# H743X___V1_0__PCB__AD.net
KiCad netlist of a schematic drawn in Altium Designer
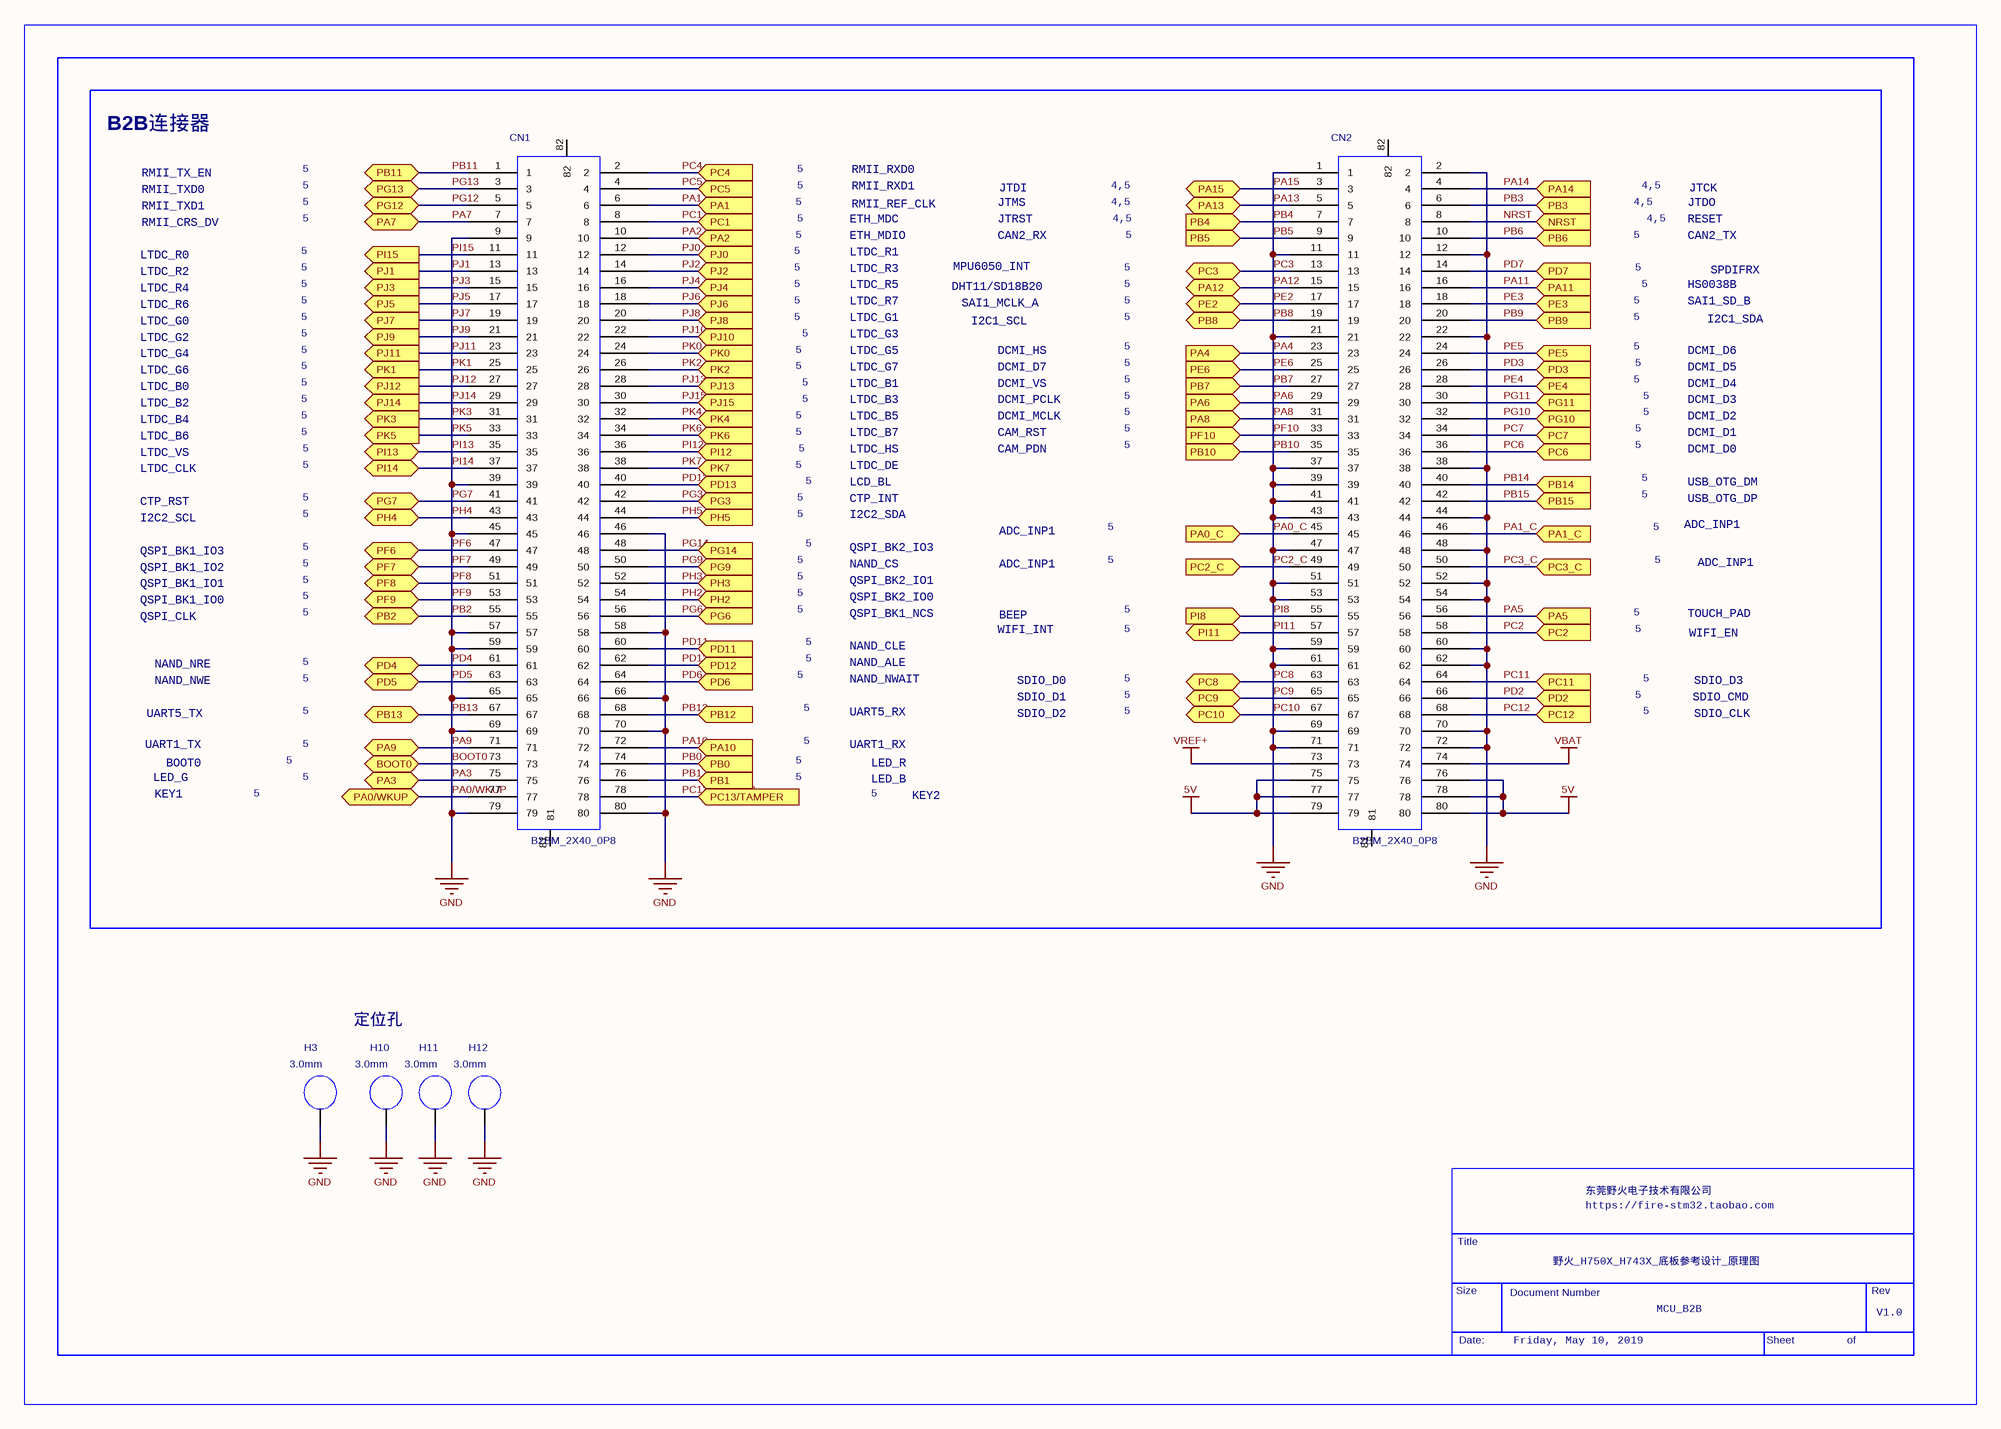
[diagram p0: 野火_H743X_核心板_V1.0_底板原理图和PCB参考设计_AD格式.SchDoc]

(export (version "E")
  (design (tool "Eeschema 10.0.6"))
  (components
    (comp (ref "CN1")
      (value "B2BM_2X40_0P8")
      (footprint "B2BM-2X40-0P8")
      (fields
        (field (name "Comment") "B2BF_2X40_0")
        (field (name "SOURCE_PATH") "F:\\STM32\\H750\\SCH\\野火_H750 PRO底板_原理图_V1_0.DSN")
      )
      (libsource (lib "*") (part "B2BF_2X40_0"))
    )
    (comp (ref "CN2")
      (value "B2BM_2X40_0P8")
      (footprint "B2BM-2X40-0P8")
      (fields
        (field (name "Comment") "B2BF_2X40_0")
        (field (name "SOURCE_PATH") "F:\\STM32\\H750\\SCH\\野火_H750 PRO底板_原理图_V1_0.DSN")
      )
      (libsource (lib "*") (part "B2BF_2X40_0"))
    )
    (comp (ref "H3")
      (value "3.0mm")
      (footprint "T4R2-6R2_TOPSMT")
      (description "FASTENER, STANDOFF 4.5MMX3.53XM3.0X0.5 ROUND THR .635\"L BRASS")
      (fields (field (name "Comment") "SPACER_0"))
      (libsource (lib "*") (part "SPACER_0"))
    )
    (comp (ref "H10")
      (value "3.0mm")
      (footprint "T4R2-6R2_TOPSMT")
      (description "FASTENER, STANDOFF 4.5MMX3.53XM3.0X0.5 ROUND THR .635\"L BRASS")
      (fields (field (name "Comment") "SPACER_0"))
      (libsource (lib "*") (part "SPACER_0"))
    )
    (comp (ref "H11")
      (value "3.0mm")
      (footprint "T4R2-6R2_TOPSMT")
      (description "FASTENER, STANDOFF 4.5MMX3.53XM3.0X0.5 ROUND THR .635\"L BRASS")
      (fields (field (name "Comment") "SPACER_0"))
      (libsource (lib "*") (part "SPACER_0"))
    )
    (comp (ref "H12")
      (value "3.0mm")
      (footprint "T4R2-6R2_TOPSMT")
      (description "FASTENER, STANDOFF 4.5MMX3.53XM3.0X0.5 ROUND THR .635\"L BRASS")
      (fields (field (name "Comment") "SPACER_0"))
      (libsource (lib "*") (part "SPACER_0"))
    )
  )
  (nets
    (net (code "1") (name "/NRST") (class "Default")
      (node (ref "CN2") (pin "8") (pinfunction "8_8") (pintype "passive"))
    )
    (net (code "2") (name "/PA1") (class "Default")
      (node (ref "CN1") (pin "6") (pinfunction "6_6") (pintype "passive"))
    )
    (net (code "3") (name "/PA1_C") (class "Default")
      (node (ref "CN2") (pin "46") (pinfunction "46_46") (pintype "passive"))
    )
    (net (code "4") (name "/PA2") (class "Default")
      (node (ref "CN1") (pin "10") (pinfunction "10_10") (pintype "passive"))
    )
    (net (code "5") (name "/PA5") (class "Default")
      (node (ref "CN2") (pin "56") (pinfunction "56_56") (pintype "passive"))
    )
    (net (code "6") (name "/PA7") (class "Default")
      (node (ref "CN1") (pin "7") (pinfunction "7_7") (pintype "passive"))
    )
    (net (code "7") (name "/PA10") (class "Default")
      (node (ref "CN1") (pin "72") (pinfunction "72_72") (pintype "passive"))
    )
    (net (code "8") (name "/PA11") (class "Default")
      (node (ref "CN2") (pin "16") (pinfunction "16_16") (pintype "passive"))
    )
    (net (code "9") (name "/PA14") (class "Default")
      (node (ref "CN2") (pin "4") (pinfunction "4_4") (pintype "passive"))
    )
    (net (code "10") (name "/PB0") (class "Default")
      (node (ref "CN1") (pin "74") (pinfunction "74_74") (pintype "passive"))
    )
    (net (code "11") (name "/PB1") (class "Default")
      (node (ref "CN1") (pin "76") (pinfunction "76_76") (pintype "passive"))
    )
    (net (code "12") (name "/PB3") (class "Default")
      (node (ref "CN2") (pin "6") (pinfunction "6_6") (pintype "passive"))
    )
    (net (code "13") (name "/PB6") (class "Default")
      (node (ref "CN2") (pin "10") (pinfunction "10_10") (pintype "passive"))
    )
    (net (code "14") (name "/PB9") (class "Default")
      (node (ref "CN2") (pin "20") (pinfunction "20_20") (pintype "passive"))
    )
    (net (code "15") (name "/PB11") (class "Default")
      (node (ref "CN1") (pin "1") (pinfunction "1_1") (pintype "passive"))
    )
    (net (code "16") (name "/PB12") (class "Default")
      (node (ref "CN1") (pin "68") (pinfunction "68_68") (pintype "passive"))
    )
    (net (code "17") (name "/PB14") (class "Default")
      (node (ref "CN2") (pin "40") (pinfunction "40_40") (pintype "passive"))
    )
    (net (code "18") (name "/PB15") (class "Default")
      (node (ref "CN2") (pin "42") (pinfunction "42_42") (pintype "passive"))
    )
    (net (code "19") (name "/PC1") (class "Default")
      (node (ref "CN1") (pin "8") (pinfunction "8_8") (pintype "passive"))
    )
    (net (code "20") (name "/PC2") (class "Default")
      (node (ref "CN2") (pin "58") (pinfunction "58_58") (pintype "passive"))
    )
    (net (code "21") (name "/PC3_C") (class "Default")
      (node (ref "CN2") (pin "50") (pinfunction "50_50") (pintype "passive"))
    )
    (net (code "22") (name "/PC4") (class "Default")
      (node (ref "CN1") (pin "2") (pinfunction "2_2") (pintype "passive"))
    )
    (net (code "23") (name "/PC5") (class "Default")
      (node (ref "CN1") (pin "4") (pinfunction "4_4") (pintype "passive"))
    )
    (net (code "24") (name "/PC6") (class "Default")
      (node (ref "CN2") (pin "36") (pinfunction "36_36") (pintype "passive"))
    )
    (net (code "25") (name "/PC7") (class "Default")
      (node (ref "CN2") (pin "34") (pinfunction "34_34") (pintype "passive"))
    )
    (net (code "26") (name "/PC11") (class "Default")
      (node (ref "CN2") (pin "64") (pinfunction "64_64") (pintype "passive"))
    )
    (net (code "27") (name "/PC12") (class "Default")
      (node (ref "CN2") (pin "68") (pinfunction "68_68") (pintype "passive"))
    )
    (net (code "28") (name "/PC13{slash}TAMPER") (class "Default")
      (node (ref "CN1") (pin "78") (pinfunction "78_78") (pintype "passive"))
    )
    (net (code "29") (name "/PD2") (class "Default")
      (node (ref "CN2") (pin "66") (pinfunction "66_66") (pintype "passive"))
    )
    (net (code "30") (name "/PD3") (class "Default")
      (node (ref "CN2") (pin "26") (pinfunction "26_26") (pintype "passive"))
    )
    (net (code "31") (name "/PD6") (class "Default")
      (node (ref "CN1") (pin "64") (pinfunction "64_64") (pintype "passive"))
    )
    (net (code "32") (name "/PD7") (class "Default")
      (node (ref "CN2") (pin "14") (pinfunction "14_14") (pintype "passive"))
    )
    (net (code "33") (name "/PD11") (class "Default")
      (node (ref "CN1") (pin "60") (pinfunction "60_60") (pintype "passive"))
    )
    (net (code "34") (name "/PD12") (class "Default")
      (node (ref "CN1") (pin "62") (pinfunction "62_62") (pintype "passive"))
    )
    (net (code "35") (name "/PD13") (class "Default")
      (node (ref "CN1") (pin "40") (pinfunction "40_40") (pintype "passive"))
    )
    (net (code "36") (name "/PE3") (class "Default")
      (node (ref "CN2") (pin "18") (pinfunction "18_18") (pintype "passive"))
    )
    (net (code "37") (name "/PE4") (class "Default")
      (node (ref "CN2") (pin "28") (pinfunction "28_28") (pintype "passive"))
    )
    (net (code "38") (name "/PE5") (class "Default")
      (node (ref "CN2") (pin "24") (pinfunction "24_24") (pintype "passive"))
    )
    (net (code "39") (name "/PG3") (class "Default")
      (node (ref "CN1") (pin "42") (pinfunction "42_42") (pintype "passive"))
    )
    (net (code "40") (name "/PG6") (class "Default")
      (node (ref "CN1") (pin "56") (pinfunction "56_56") (pintype "passive"))
    )
    (net (code "41") (name "/PG9") (class "Default")
      (node (ref "CN1") (pin "50") (pinfunction "50_50") (pintype "passive"))
    )
    (net (code "42") (name "/PG10") (class "Default")
      (node (ref "CN2") (pin "32") (pinfunction "32_32") (pintype "passive"))
    )
    (net (code "43") (name "/PG11") (class "Default")
      (node (ref "CN2") (pin "30") (pinfunction "30_30") (pintype "passive"))
    )
    (net (code "44") (name "/PG12") (class "Default")
      (node (ref "CN1") (pin "5") (pinfunction "5_5") (pintype "passive"))
    )
    (net (code "45") (name "/PG13") (class "Default")
      (node (ref "CN1") (pin "3") (pinfunction "3_3") (pintype "passive"))
    )
    (net (code "46") (name "/PG14") (class "Default")
      (node (ref "CN1") (pin "48") (pinfunction "48_48") (pintype "passive"))
    )
    (net (code "47") (name "/PH2") (class "Default")
      (node (ref "CN1") (pin "54") (pinfunction "54_54") (pintype "passive"))
    )
    (net (code "48") (name "/PH3") (class "Default")
      (node (ref "CN1") (pin "52") (pinfunction "52_52") (pintype "passive"))
    )
    (net (code "49") (name "/PH5") (class "Default")
      (node (ref "CN1") (pin "44") (pinfunction "44_44") (pintype "passive"))
    )
    (net (code "50") (name "/PI12") (class "Default")
      (node (ref "CN1") (pin "36") (pinfunction "36_36") (pintype "passive"))
    )
    (net (code "51") (name "/PJ0") (class "Default")
      (node (ref "CN1") (pin "12") (pinfunction "12_12") (pintype "passive"))
    )
    (net (code "52") (name "/PJ2") (class "Default")
      (node (ref "CN1") (pin "14") (pinfunction "14_14") (pintype "passive"))
    )
    (net (code "53") (name "/PJ4") (class "Default")
      (node (ref "CN1") (pin "16") (pinfunction "16_16") (pintype "passive"))
    )
    (net (code "54") (name "/PJ6") (class "Default")
      (node (ref "CN1") (pin "18") (pinfunction "18_18") (pintype "passive"))
    )
    (net (code "55") (name "/PJ8") (class "Default")
      (node (ref "CN1") (pin "20") (pinfunction "20_20") (pintype "passive"))
    )
    (net (code "56") (name "/PJ10") (class "Default")
      (node (ref "CN1") (pin "22") (pinfunction "22_22") (pintype "passive"))
    )
    (net (code "57") (name "/PJ13") (class "Default")
      (node (ref "CN1") (pin "28") (pinfunction "28_28") (pintype "passive"))
    )
    (net (code "58") (name "/PJ15") (class "Default")
      (node (ref "CN1") (pin "30") (pinfunction "30_30") (pintype "passive"))
    )
    (net (code "59") (name "/PK0") (class "Default")
      (node (ref "CN1") (pin "24") (pinfunction "24_24") (pintype "passive"))
    )
    (net (code "60") (name "/PK2") (class "Default")
      (node (ref "CN1") (pin "26") (pinfunction "26_26") (pintype "passive"))
    )
    (net (code "61") (name "/PK4") (class "Default")
      (node (ref "CN1") (pin "32") (pinfunction "32_32") (pintype "passive"))
    )
    (net (code "62") (name "/PK6") (class "Default")
      (node (ref "CN1") (pin "34") (pinfunction "34_34") (pintype "passive"))
    )
    (net (code "63") (name "/PK7") (class "Default")
      (node (ref "CN1") (pin "38") (pinfunction "38_38") (pintype "passive"))
    )
    (net (code "64") (name "5V") (class "Default")
      (node (ref "CN2") (pin "75") (pinfunction "75_75") (pintype "passive"))
      (node (ref "CN2") (pin "76") (pinfunction "76_76") (pintype "passive"))
      (node (ref "CN2") (pin "77") (pinfunction "77_77") (pintype "passive"))
      (node (ref "CN2") (pin "78") (pinfunction "78_78") (pintype "passive"))
      (node (ref "CN2") (pin "79") (pinfunction "79_79") (pintype "passive"))
      (node (ref "CN2") (pin "80") (pinfunction "80_80") (pintype "passive"))
    )
    (net (code "65") (name "GND") (class "Default")
      (node (ref "CN1") (pin "11") (pinfunction "11_11") (pintype "passive"))
      (node (ref "CN1") (pin "13") (pinfunction "13_13") (pintype "passive"))
      (node (ref "CN1") (pin "15") (pinfunction "15_15") (pintype "passive"))
      (node (ref "CN1") (pin "17") (pinfunction "17_17") (pintype "passive"))
      (node (ref "CN1") (pin "19") (pinfunction "19_19") (pintype "passive"))
      (node (ref "CN1") (pin "21") (pinfunction "21_21") (pintype "passive"))
      (node (ref "CN1") (pin "23") (pinfunction "23_23") (pintype "passive"))
      (node (ref "CN1") (pin "25") (pinfunction "25_25") (pintype "passive"))
      (node (ref "CN1") (pin "27") (pinfunction "27_27") (pintype "passive"))
      (node (ref "CN1") (pin "29") (pinfunction "29_29") (pintype "passive"))
      (node (ref "CN1") (pin "31") (pinfunction "31_31") (pintype "passive"))
      (node (ref "CN1") (pin "33") (pinfunction "33_33") (pintype "passive"))
      (node (ref "CN1") (pin "35") (pinfunction "35_35") (pintype "passive"))
      (node (ref "CN1") (pin "37") (pinfunction "37_37") (pintype "passive"))
      (node (ref "CN1") (pin "39") (pinfunction "39_39") (pintype "passive"))
      (node (ref "CN1") (pin "41") (pinfunction "41_41") (pintype "passive"))
      (node (ref "CN1") (pin "43") (pinfunction "43_43") (pintype "passive"))
      (node (ref "CN1") (pin "45") (pinfunction "45_45") (pintype "passive"))
      (node (ref "CN1") (pin "46") (pinfunction "46_46") (pintype "passive"))
      (node (ref "CN1") (pin "47") (pinfunction "47_47") (pintype "passive"))
      (node (ref "CN1") (pin "49") (pinfunction "49_49") (pintype "passive"))
      (node (ref "CN1") (pin "51") (pinfunction "51_51") (pintype "passive"))
      (node (ref "CN1") (pin "53") (pinfunction "53_53") (pintype "passive"))
      (node (ref "CN1") (pin "55") (pinfunction "55_55") (pintype "passive"))
      (node (ref "CN1") (pin "57") (pinfunction "57_57") (pintype "passive"))
      (node (ref "CN1") (pin "58") (pinfunction "58_58") (pintype "passive"))
      (node (ref "CN1") (pin "59") (pinfunction "59_59") (pintype "passive"))
      (node (ref "CN1") (pin "61") (pinfunction "61_61") (pintype "passive"))
      (node (ref "CN1") (pin "63") (pinfunction "63_63") (pintype "passive"))
      (node (ref "CN1") (pin "65") (pinfunction "65_65") (pintype "passive"))
      (node (ref "CN1") (pin "66") (pinfunction "66_66") (pintype "passive"))
      (node (ref "CN1") (pin "67") (pinfunction "67_67") (pintype "passive"))
      (node (ref "CN1") (pin "69") (pinfunction "69_69") (pintype "passive"))
      (node (ref "CN1") (pin "70") (pinfunction "70_70") (pintype "passive"))
      (node (ref "CN1") (pin "71") (pinfunction "71_71") (pintype "passive"))
      (node (ref "CN1") (pin "73") (pinfunction "73_73") (pintype "passive"))
      (node (ref "CN1") (pin "75") (pinfunction "75_75") (pintype "passive"))
      (node (ref "CN1") (pin "77") (pinfunction "77_77") (pintype "passive"))
      (node (ref "CN1") (pin "79") (pinfunction "79_79") (pintype "passive"))
      (node (ref "CN1") (pin "80") (pinfunction "80_80") (pintype "passive"))
      (node (ref "CN1") (pin "9") (pinfunction "9_9") (pintype "passive"))
      (node (ref "CN2") (pin "1") (pinfunction "1_1") (pintype "passive"))
      (node (ref "CN2") (pin "11") (pinfunction "11_11") (pintype "passive"))
      (node (ref "CN2") (pin "12") (pinfunction "12_12") (pintype "passive"))
      (node (ref "CN2") (pin "13") (pinfunction "13_13") (pintype "passive"))
      (node (ref "CN2") (pin "15") (pinfunction "15_15") (pintype "passive"))
      (node (ref "CN2") (pin "17") (pinfunction "17_17") (pintype "passive"))
      (node (ref "CN2") (pin "19") (pinfunction "19_19") (pintype "passive"))
      (node (ref "CN2") (pin "2") (pinfunction "2_2") (pintype "passive"))
      (node (ref "CN2") (pin "21") (pinfunction "21_21") (pintype "passive"))
      (node (ref "CN2") (pin "22") (pinfunction "22_22") (pintype "passive"))
      (node (ref "CN2") (pin "23") (pinfunction "23_23") (pintype "passive"))
      (node (ref "CN2") (pin "25") (pinfunction "25_25") (pintype "passive"))
      (node (ref "CN2") (pin "27") (pinfunction "27_27") (pintype "passive"))
      (node (ref "CN2") (pin "29") (pinfunction "29_29") (pintype "passive"))
      (node (ref "CN2") (pin "3") (pinfunction "3_3") (pintype "passive"))
      (node (ref "CN2") (pin "31") (pinfunction "31_31") (pintype "passive"))
      (node (ref "CN2") (pin "33") (pinfunction "33_33") (pintype "passive"))
      (node (ref "CN2") (pin "35") (pinfunction "35_35") (pintype "passive"))
      (node (ref "CN2") (pin "37") (pinfunction "37_37") (pintype "passive"))
      (node (ref "CN2") (pin "38") (pinfunction "38_38") (pintype "passive"))
      (node (ref "CN2") (pin "39") (pinfunction "39_39") (pintype "passive"))
      (node (ref "CN2") (pin "41") (pinfunction "41_41") (pintype "passive"))
      (node (ref "CN2") (pin "43") (pinfunction "43_43") (pintype "passive"))
      (node (ref "CN2") (pin "44") (pinfunction "44_44") (pintype "passive"))
      (node (ref "CN2") (pin "45") (pinfunction "45_45") (pintype "passive"))
      (node (ref "CN2") (pin "47") (pinfunction "47_47") (pintype "passive"))
      (node (ref "CN2") (pin "48") (pinfunction "48_48") (pintype "passive"))
      (node (ref "CN2") (pin "49") (pinfunction "49_49") (pintype "passive"))
      (node (ref "CN2") (pin "5") (pinfunction "5_5") (pintype "passive"))
      (node (ref "CN2") (pin "51") (pinfunction "51_51") (pintype "passive"))
      (node (ref "CN2") (pin "52") (pinfunction "52_52") (pintype "passive"))
      (node (ref "CN2") (pin "53") (pinfunction "53_53") (pintype "passive"))
      (node (ref "CN2") (pin "54") (pinfunction "54_54") (pintype "passive"))
      (node (ref "CN2") (pin "55") (pinfunction "55_55") (pintype "passive"))
      (node (ref "CN2") (pin "57") (pinfunction "57_57") (pintype "passive"))
      (node (ref "CN2") (pin "59") (pinfunction "59_59") (pintype "passive"))
      (node (ref "CN2") (pin "60") (pinfunction "60_60") (pintype "passive"))
      (node (ref "CN2") (pin "61") (pinfunction "61_61") (pintype "passive"))
      (node (ref "CN2") (pin "62") (pinfunction "62_62") (pintype "passive"))
      (node (ref "CN2") (pin "63") (pinfunction "63_63") (pintype "passive"))
      (node (ref "CN2") (pin "65") (pinfunction "65_65") (pintype "passive"))
      (node (ref "CN2") (pin "67") (pinfunction "67_67") (pintype "passive"))
      (node (ref "CN2") (pin "69") (pinfunction "69_69") (pintype "passive"))
      (node (ref "CN2") (pin "7") (pinfunction "7_7") (pintype "passive"))
      (node (ref "CN2") (pin "70") (pinfunction "70_70") (pintype "passive"))
      (node (ref "CN2") (pin "71") (pinfunction "71_71") (pintype "passive"))
      (node (ref "CN2") (pin "72") (pinfunction "72_72") (pintype "passive"))
      (node (ref "CN2") (pin "9") (pinfunction "9_9") (pintype "passive"))
      (node (ref "H10") (pin "1") (pinfunction "NC_1_1") (pintype "passive"))
      (node (ref "H11") (pin "1") (pinfunction "NC_1_1") (pintype "passive"))
      (node (ref "H12") (pin "1") (pinfunction "NC_1_1") (pintype "passive"))
      (node (ref "H3") (pin "1") (pinfunction "NC_1_1") (pintype "passive"))
    )
    (net (code "66") (name "VBAT") (class "Default")
      (node (ref "CN2") (pin "74") (pinfunction "74_74") (pintype "passive"))
    )
    (net (code "67") (name "VREF+") (class "Default")
      (node (ref "CN2") (pin "73") (pinfunction "73_73") (pintype "passive"))
    )
    (net (code "68") (name "unconnected-(CN1-Pad81)") (class "Default")
      (node (ref "CN1") (pin "81") (pinfunction "81_81") (pintype "passive"))
    )
    (net (code "69") (name "unconnected-(CN1-Pad82)") (class "Default")
      (node (ref "CN1") (pin "82") (pinfunction "82_82") (pintype "passive"))
    )
    (net (code "70") (name "unconnected-(CN2-Pad81)") (class "Default")
      (node (ref "CN2") (pin "81") (pinfunction "81_81") (pintype "passive"))
    )
    (net (code "71") (name "unconnected-(CN2-Pad82)") (class "Default")
      (node (ref "CN2") (pin "82") (pinfunction "82_82") (pintype "passive"))
    )
  )
)
